# recall_discrete_v0_1.net
KiCad netlist of a schematic drawn in Altium Designer
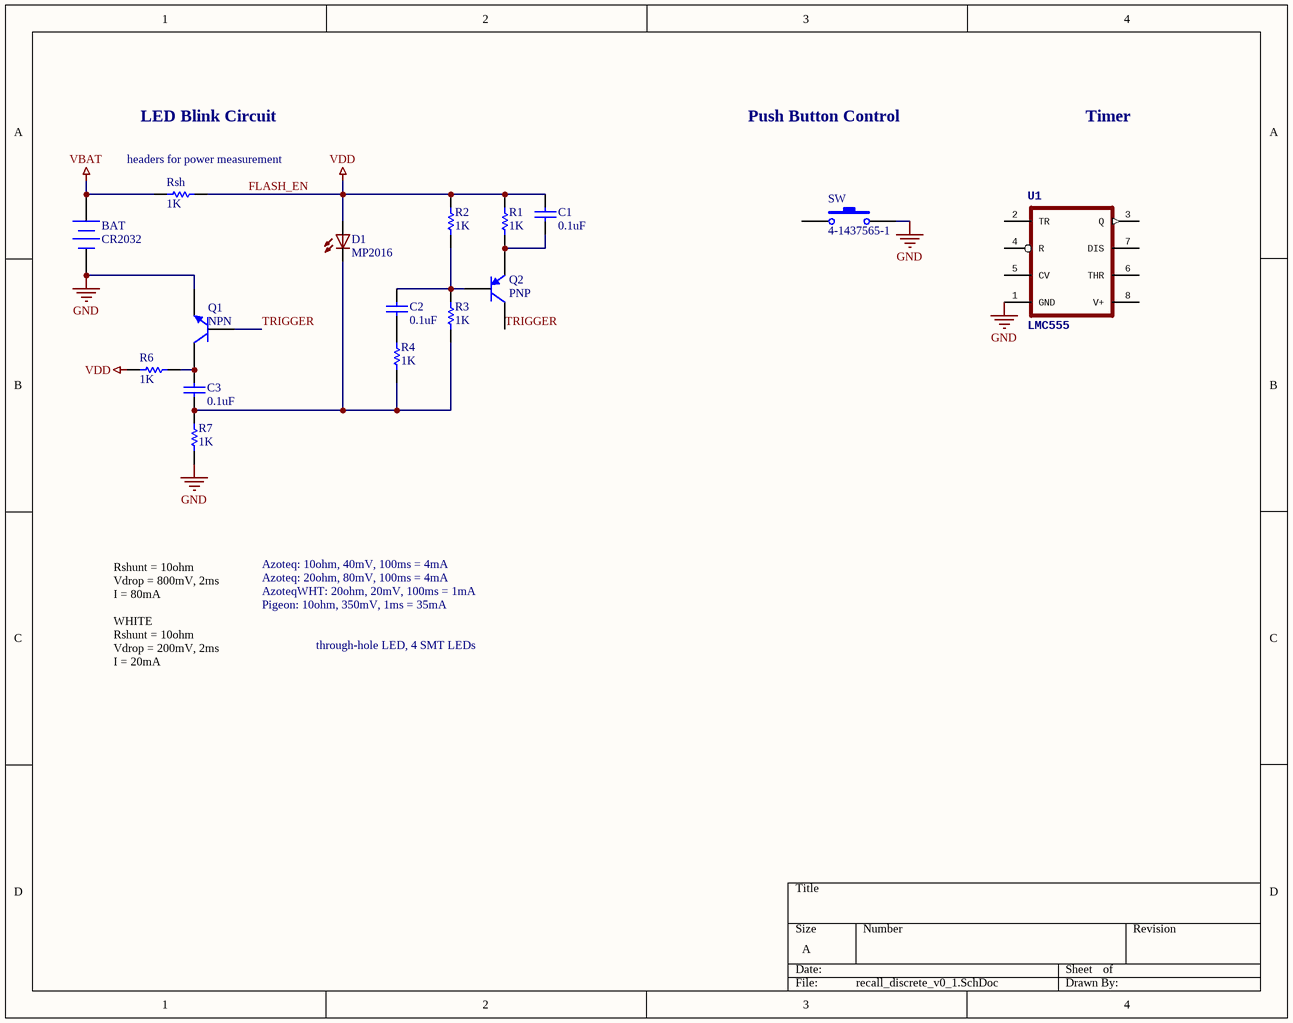
[diagram p0: recall_discrete_v0_1.SchDoc]

(export (version "E")
  (design (tool "Eeschema 10.0.6"))
  (components
    (comp (ref "BAT")
      (value "CR2032")
      (footprint "BAT-HLD-001")
      (fields (field (name "PUBLISHER") "Altium Limited"))
      (libsource (lib "recall") (part "Battery"))
    )
    (comp (ref "C1")
      (value "0.1uF")
      (footprint "CAP_0402R")
      (description "Capacitor")
      (fields (field (name "Comment") "CAP") (field (name "PUBLISHER") "Altium Limited"))
      (libsource (lib "recall") (part "CAP"))
    )
    (comp (ref "C2")
      (value "0.1uF")
      (footprint "CAP_0402R")
      (description "Capacitor")
      (fields (field (name "Comment") "CAP") (field (name "PUBLISHER") "Altium Limited"))
      (libsource (lib "recall") (part "CAP"))
    )
    (comp (ref "C3")
      (value "0.1uF")
      (footprint "CAP_0402R")
      (description "Capacitor")
      (fields (field (name "Comment") "CAP") (field (name "PUBLISHER") "Altium Limited"))
      (libsource (lib "recall") (part "CAP"))
    )
    (comp (ref "D1")
      (value "MP2016")
      (footprint "MP2016_centered")
      (description "MP2016 White LED")
      (libsource (lib "recall") (part "MP2016"))
    )
    (comp (ref "Q1")
      (value "NPN")
      (footprint "SOT-23")
      (description "NPN General Purpose Transistor, 2N3904, MMBT2222AL")
      (fields (field (name "PUBLISHER") "Altium Limited"))
      (libsource (lib "recall") (part "NPN"))
    )
    (comp (ref "Q2")
      (value "PNP")
      (footprint "SOT-23")
      (description "PNP General Purpose Transistor, 2N3906, MMBT2907AL")
      (fields (field (name "PUBLISHER") "Altium Limited"))
      (libsource (lib "recall") (part "PNP"))
    )
    (comp (ref "R1")
      (value "1K")
      (footprint "RES_0402")
      (description "Resistor")
      (fields (field (name "Comment") "RES") (field (name "PUBLISHER") "Altium Limited"))
      (libsource (lib "recall") (part "RES"))
    )
    (comp (ref "R2")
      (value "1K")
      (footprint "RES_0402")
      (description "Resistor")
      (fields (field (name "Comment") "RES") (field (name "PUBLISHER") "Altium Limited"))
      (libsource (lib "recall") (part "RES"))
    )
    (comp (ref "R3")
      (value "1K")
      (footprint "RES_0402")
      (description "Resistor")
      (fields (field (name "Comment") "RES") (field (name "PUBLISHER") "Altium Limited"))
      (libsource (lib "recall") (part "RES"))
    )
    (comp (ref "R4")
      (value "1K")
      (footprint "RES_0402")
      (description "Resistor")
      (fields (field (name "Comment") "RES") (field (name "PUBLISHER") "Altium Limited"))
      (libsource (lib "recall") (part "RES"))
    )
    (comp (ref "R6")
      (value "1K")
      (footprint "RES_0402")
      (description "Resistor")
      (fields (field (name "Comment") "RES") (field (name "PUBLISHER") "Altium Limited"))
      (libsource (lib "recall") (part "RES"))
    )
    (comp (ref "R7")
      (value "1K")
      (footprint "RES_0402")
      (description "Resistor")
      (fields (field (name "Comment") "RES") (field (name "PUBLISHER") "Altium Limited"))
      (libsource (lib "recall") (part "RES"))
    )
    (comp (ref "Rsh")
      (value "1K")
      (footprint "RES_0402")
      (description "Resistor")
      (fields (field (name "Comment") "RES") (field (name "PUBLISHER") "Altium Limited"))
      (libsource (lib "recall") (part "RES"))
    )
    (comp (ref "SW")
      (value "4-1437565-1")
      (footprint "4-1437565-1")
      (description "Translucent Conductive Silicone Elastomer Switch")
      (fields (field (name "PUBLISHER") "Altium Limited"))
      (libsource (lib "recall") (part "SW-TACT"))
    )
    (comp (ref "U1") (value "LMC555") (footprint "SOIC-8") (libsource (lib "recall") (part "LMC555")))
  )
  (nets
    (net (code "1") (name "/TRIGGER") (class "Default")
      (node (ref "Q1") (pin "1") (pinfunction "B_1") (pintype "passive"))
      (node (ref "Q2") (pin "3") (pinfunction "C_3") (pintype "passive"))
    )
    (net (code "2") (name "GND") (class "Default")
      (node (ref "BAT") (pin "2") (pinfunction "-_2") (pintype "passive"))
      (node (ref "Q1") (pin "2") (pinfunction "E_2") (pintype "passive"))
      (node (ref "R7") (pin "1") (pinfunction "1_1") (pintype "passive"))
      (node (ref "SW") (pin "2") (pinfunction "2_2") (pintype "passive"))
      (node (ref "U1") (pin "1") (pinfunction "GND_1") (pintype "power_in"))
    )
    (net (code "3") (name "Net-(C2-Pad2)") (class "Default")
      (node (ref "C2") (pin "2") (pinfunction "2_2") (pintype "passive"))
      (node (ref "R4") (pin "2") (pinfunction "2_2") (pintype "passive"))
    )
    (net (code "4") (name "Net-(C3-Pad1)") (class "Default")
      (node (ref "C3") (pin "1") (pinfunction "1_1") (pintype "passive"))
      (node (ref "D1") (pin "C") (pinfunction "C_C") (pintype "passive"))
      (node (ref "R3") (pin "1") (pinfunction "1_1") (pintype "passive"))
      (node (ref "R4") (pin "1") (pinfunction "1_1") (pintype "passive"))
      (node (ref "R7") (pin "2") (pinfunction "2_2") (pintype "passive"))
    )
    (net (code "5") (name "Net-(Q1-C)") (class "Default")
      (node (ref "C3") (pin "2") (pinfunction "2_2") (pintype "passive"))
      (node (ref "Q1") (pin "3") (pinfunction "C_3") (pintype "passive"))
      (node (ref "R6") (pin "1") (pinfunction "1_1") (pintype "passive"))
    )
    (net (code "6") (name "Net-(Q2-B)") (class "Default")
      (node (ref "C2") (pin "1") (pinfunction "1_1") (pintype "passive"))
      (node (ref "Q2") (pin "1") (pinfunction "B_1") (pintype "passive"))
      (node (ref "R2") (pin "1") (pinfunction "1_1") (pintype "passive"))
      (node (ref "R3") (pin "2") (pinfunction "2_2") (pintype "passive"))
    )
    (net (code "7") (name "Net-(Q2-E)") (class "Default")
      (node (ref "C1") (pin "1") (pinfunction "1_1") (pintype "passive"))
      (node (ref "Q2") (pin "2") (pinfunction "E_2") (pintype "passive"))
      (node (ref "R1") (pin "1") (pinfunction "1_1") (pintype "passive"))
    )
    (net (code "8") (name "VBAT") (class "Default")
      (node (ref "BAT") (pin "1") (pinfunction "+_1") (pintype "passive"))
      (node (ref "Rsh") (pin "2") (pinfunction "2_2") (pintype "passive"))
    )
    (net (code "9") (name "VDD") (class "Default")
      (node (ref "C1") (pin "2") (pinfunction "2_2") (pintype "passive"))
      (node (ref "D1") (pin "A") (pinfunction "A_A") (pintype "passive"))
      (node (ref "R1") (pin "2") (pinfunction "2_2") (pintype "passive"))
      (node (ref "R2") (pin "2") (pinfunction "2_2") (pintype "passive"))
      (node (ref "R6") (pin "2") (pinfunction "2_2") (pintype "passive"))
      (node (ref "Rsh") (pin "1") (pinfunction "1_1") (pintype "passive"))
    )
    (net (code "10") (name "unconnected-(SW-Pad1)") (class "Default")
      (node (ref "SW") (pin "1") (pinfunction "1_1") (pintype "passive"))
    )
    (net (code "11") (name "unconnected-(U1-CV-Pad5)") (class "Default")
      (node (ref "U1") (pin "5") (pinfunction "CV_5") (pintype "passive"))
    )
    (net (code "12") (name "unconnected-(U1-DIS-Pad7)") (class "Default")
      (node (ref "U1") (pin "7") (pinfunction "DIS_7") (pintype "passive"))
    )
    (net (code "13") (name "unconnected-(U1-Q-Pad3)") (class "Default")
      (node (ref "U1") (pin "3") (pinfunction "Q_3") (pintype "output"))
    )
    (net (code "14") (name "unconnected-(U1-R-Pad4)") (class "Default")
      (node (ref "U1") (pin "4") (pinfunction "R_4") (pintype "passive"))
    )
    (net (code "15") (name "unconnected-(U1-THR-Pad6)") (class "Default")
      (node (ref "U1") (pin "6") (pinfunction "THR_6") (pintype "passive"))
    )
    (net (code "16") (name "unconnected-(U1-TR-Pad2)") (class "Default")
      (node (ref "U1") (pin "2") (pinfunction "TR_2") (pintype "passive"))
    )
    (net (code "17") (name "unconnected-(U1-V+-Pad8)") (class "Default")
      (node (ref "U1") (pin "8") (pinfunction "V+_8") (pintype "power_in"))
    )
  )
)
